# STM_BLOCK.net
KiCad netlist of a schematic drawn in EAGLE
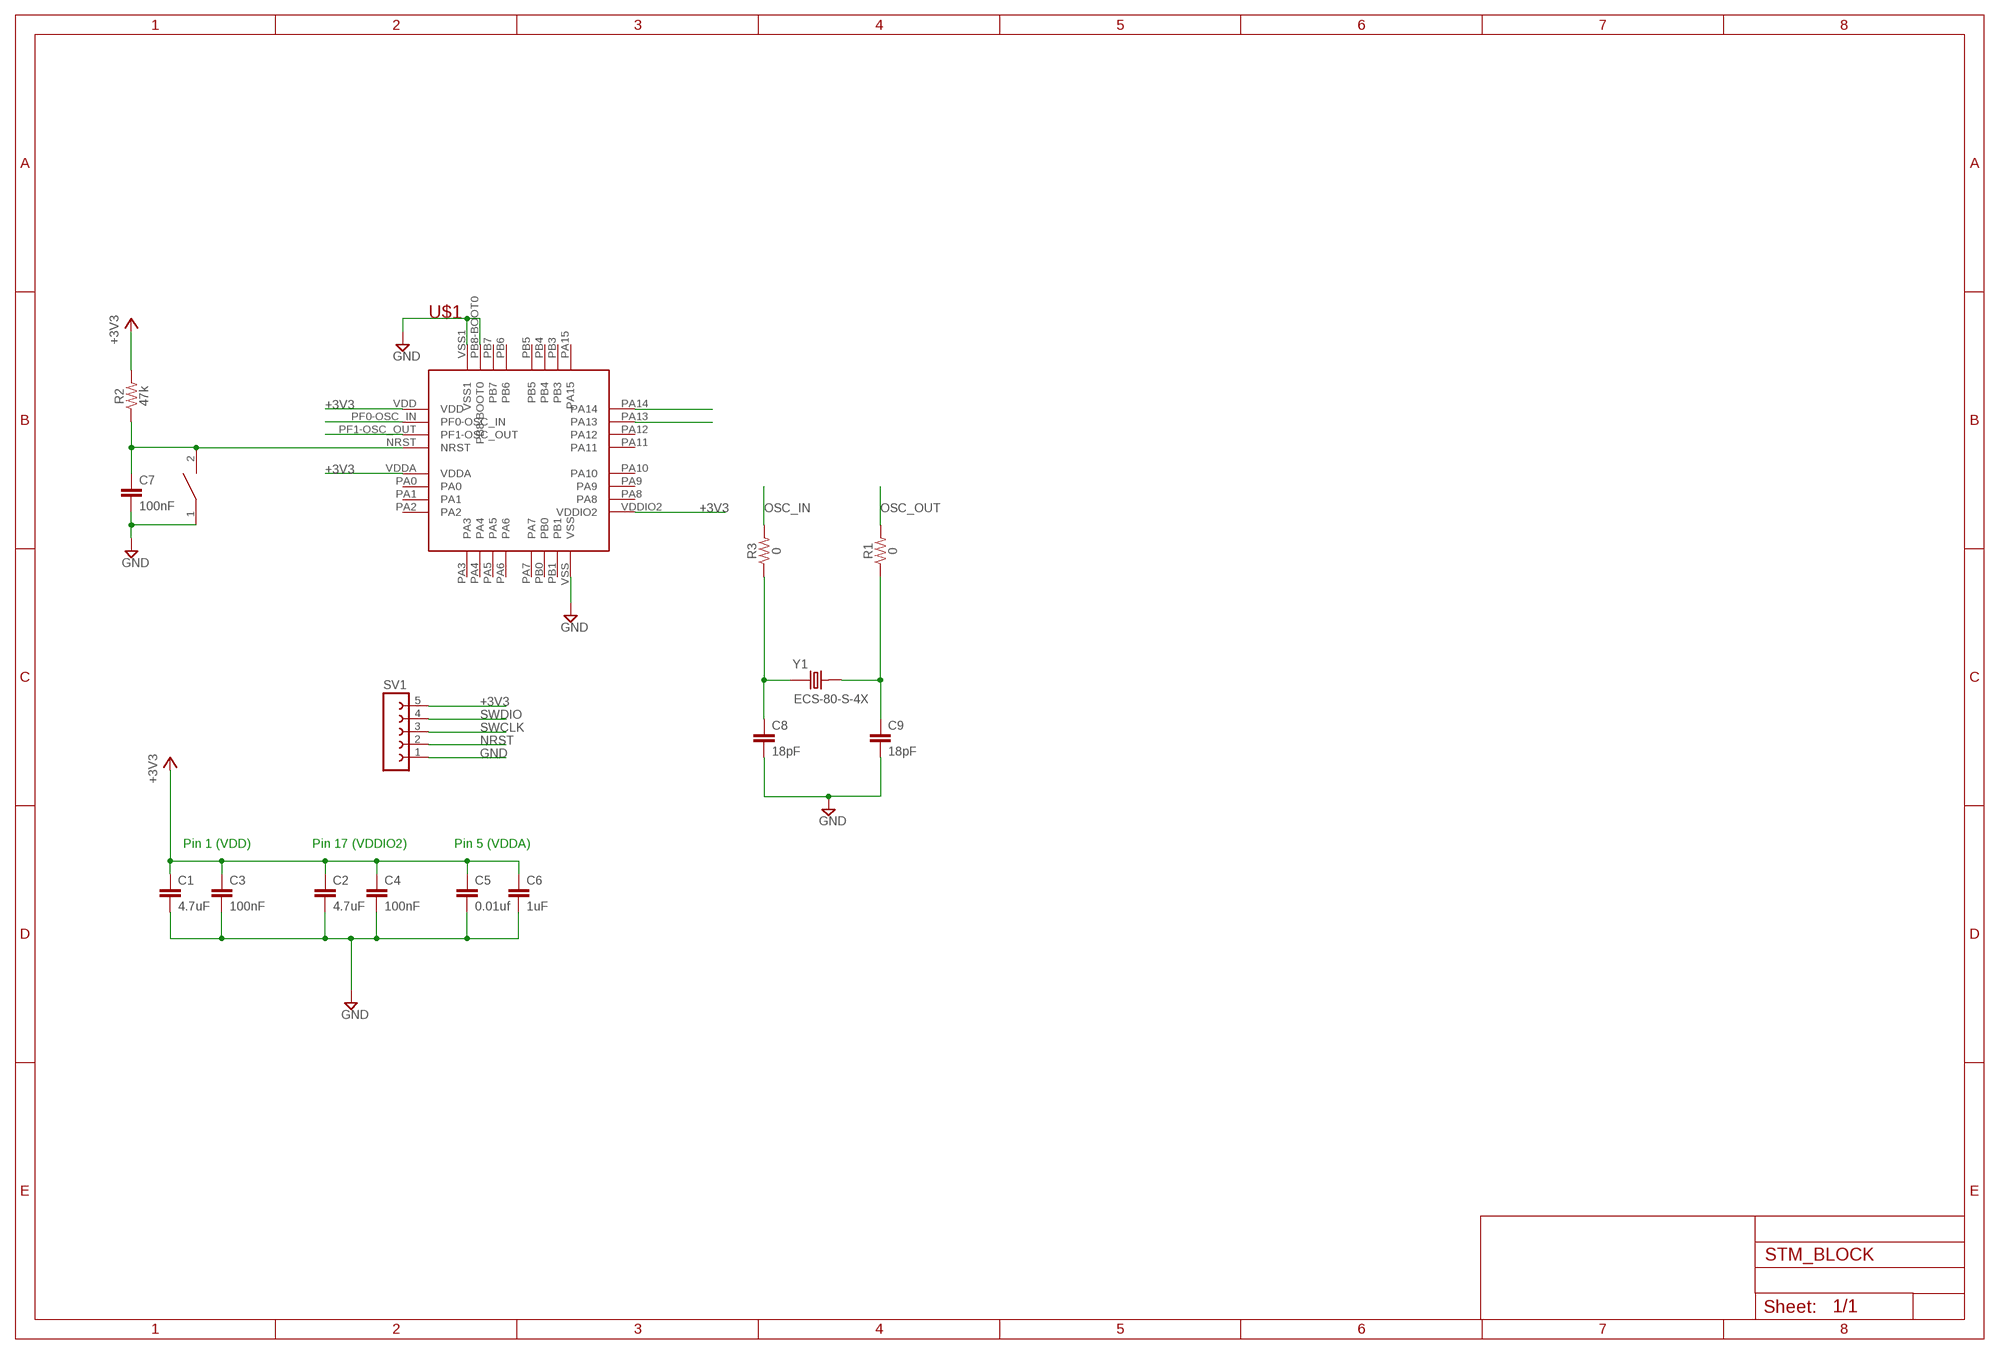
[diagram p0: schematic, sheet 1]

(export (version "E")
  (design (tool "Eeschema 10.0.6"))
  (components
    (comp (ref "C1")
      (value "4.7uF")
      (footprint "eagle-import:0603")
      (libsource (lib "eagle-import") (part "4.7UF0603"))
    )
    (comp (ref "C2")
      (value "4.7uF")
      (footprint "eagle-import:0603")
      (libsource (lib "eagle-import") (part "4.7UF0603"))
    )
    (comp (ref "C3")
      (value "100nF")
      (footprint "eagle-import:0603")
      (libsource (lib "eagle-import") (part "4.7UF0603"))
    )
    (comp (ref "C4")
      (value "100nF")
      (footprint "eagle-import:0603")
      (libsource (lib "eagle-import") (part "4.7UF0603"))
    )
    (comp (ref "C5")
      (value "0.01uf")
      (footprint "eagle-import:0603")
      (libsource (lib "eagle-import") (part "4.7UF0603"))
    )
    (comp (ref "C6")
      (value "1uF")
      (footprint "eagle-import:0603")
      (libsource (lib "eagle-import") (part "4.7UF0603"))
    )
    (comp (ref "C7")
      (value "100nF")
      (footprint "eagle-import:0603")
      (libsource (lib "eagle-import") (part "4.7UF0603"))
    )
    (comp (ref "C8")
      (value "18pF")
      (footprint "eagle-import:0603")
      (libsource (lib "eagle-import") (part "4.7UF0603"))
    )
    (comp (ref "C9")
      (value "18pF")
      (footprint "eagle-import:0603")
      (libsource (lib "eagle-import") (part "4.7UF0603"))
    )
    (comp (ref "R1")
      (value "0")
      (footprint "eagle-import:0603")
      (libsource (lib "eagle-import") (part "1KOHM-0603-1/10W-1%"))
    )
    (comp (ref "R2")
      (value "47k")
      (footprint "eagle-import:0603")
      (libsource (lib "eagle-import") (part "1KOHM-0603-1/10W-1%"))
    )
    (comp (ref "R3")
      (value "0")
      (footprint "eagle-import:0603")
      (libsource (lib "eagle-import") (part "1KOHM-0603-1/10W-1%"))
    )
    (comp (ref "RESET")
      (value "SWITCH")
      (footprint "eagle-import:SW_2512")
      (libsource (lib "eagle-import") (part "SWITCH"))
    )
    (comp (ref "SV1")
      (value "FE05-1")
      (footprint "eagle-import:FE05-1")
      (libsource (lib "eagle-import") (part "FE05-1"))
    )
    (comp (ref "U$1")
      (value "STM32F042K6T6")
      (footprint "eagle-import:STM32F042K6T6")
      (libsource (lib "eagle-import") (part "STM32F042K6T6"))
    )
    (comp (ref "Y1")
      (value "ECS-80-S-4X")
      (footprint "eagle-import:XTAL_ECS-80-S-4X")
      (fields (field (name "DIGI-KEY_PART_NUMBER") "X1057-ND") (field (name "MF") "ECS International"))
      (libsource (lib "eagle-import") (part "ECS-80-S-4X"))
    )
  )
  (nets
    (net (code "1") (name "+3V3") (class "Default")
      (node (ref "C1") (pin "1") (pinfunction "1_1") (pintype "passive"))
      (node (ref "C2") (pin "1") (pinfunction "1_1") (pintype "passive"))
      (node (ref "C3") (pin "1") (pinfunction "1_1") (pintype "passive"))
      (node (ref "C4") (pin "1") (pinfunction "1_1") (pintype "passive"))
      (node (ref "C5") (pin "1") (pinfunction "1_1") (pintype "passive"))
      (node (ref "C6") (pin "1") (pinfunction "1_1") (pintype "passive"))
      (node (ref "R2") (pin "2") (pinfunction "2_2") (pintype "passive"))
      (node (ref "SV1") (pin "5") (pinfunction "5_5") (pintype "passive"))
      (node (ref "U$1") (pin "VDD") (pinfunction "VDD_VDD") (pintype "bidirectional"))
      (node (ref "U$1") (pin "VDDA") (pinfunction "VDDA_VDDA") (pintype "bidirectional"))
      (node (ref "U$1") (pin "VDDIO2") (pinfunction "VDDIO2_VDDIO2") (pintype "bidirectional"))
    )
    (net (code "2") (name "/NRST") (class "Default")
      (node (ref "C7") (pin "1") (pinfunction "1_1") (pintype "passive"))
      (node (ref "R2") (pin "1") (pinfunction "1_1") (pintype "passive"))
      (node (ref "RESET") (pin "2") (pinfunction "P$2_2") (pintype "bidirectional"))
      (node (ref "SV1") (pin "2") (pinfunction "2_2") (pintype "passive"))
      (node (ref "U$1") (pin "NRST") (pinfunction "NRST_NRST") (pintype "bidirectional"))
    )
    (net (code "3") (name "/OSC_IN") (class "Default")
      (node (ref "R3") (pin "2") (pinfunction "2_2") (pintype "passive"))
      (node (ref "U$1") (pin "PF0-OSC_IN") (pinfunction "PF0-OSC_IN_PF0-OSC_IN") (pintype "bidirectional"))
    )
    (net (code "4") (name "/OSC_OUT") (class "Default")
      (node (ref "R1") (pin "2") (pinfunction "2_2") (pintype "passive"))
      (node (ref "U$1") (pin "PF1-OSC_OUT") (pinfunction "PF1-OSC_OUT_PF1-OSC_OUT") (pintype "bidirectional"))
    )
    (net (code "5") (name "/SWCLK") (class "Default")
      (node (ref "SV1") (pin "3") (pinfunction "3_3") (pintype "passive"))
      (node (ref "U$1") (pin "PA14") (pinfunction "PA14_PA14") (pintype "bidirectional"))
    )
    (net (code "6") (name "/SWDIO") (class "Default")
      (node (ref "SV1") (pin "4") (pinfunction "4_4") (pintype "passive"))
      (node (ref "U$1") (pin "PA13") (pinfunction "PA13_PA13") (pintype "bidirectional"))
    )
    (net (code "7") (name "GND") (class "Default")
      (node (ref "C1") (pin "2") (pinfunction "2_2") (pintype "passive"))
      (node (ref "C2") (pin "2") (pinfunction "2_2") (pintype "passive"))
      (node (ref "C3") (pin "2") (pinfunction "2_2") (pintype "passive"))
      (node (ref "C4") (pin "2") (pinfunction "2_2") (pintype "passive"))
      (node (ref "C5") (pin "2") (pinfunction "2_2") (pintype "passive"))
      (node (ref "C6") (pin "2") (pinfunction "2_2") (pintype "passive"))
      (node (ref "C7") (pin "2") (pinfunction "2_2") (pintype "passive"))
      (node (ref "C8") (pin "2") (pinfunction "2_2") (pintype "passive"))
      (node (ref "C9") (pin "2") (pinfunction "2_2") (pintype "passive"))
      (node (ref "RESET") (pin "1") (pinfunction "P$1_1") (pintype "bidirectional"))
      (node (ref "SV1") (pin "1") (pinfunction "1_1") (pintype "passive"))
      (node (ref "U$1") (pin "PB8-BOOT0") (pinfunction "PB8-BOOT0_PB8-BOOT0") (pintype "bidirectional"))
      (node (ref "U$1") (pin "VSS") (pinfunction "VSS_VSS") (pintype "bidirectional"))
      (node (ref "U$1") (pin "VSS1") (pinfunction "VSS1_VSS1") (pintype "bidirectional"))
    )
    (net (code "8") (name "Net-(C8-Pad1)") (class "Default")
      (node (ref "C8") (pin "1") (pinfunction "1_1") (pintype "passive"))
      (node (ref "R3") (pin "1") (pinfunction "1_1") (pintype "passive"))
      (node (ref "Y1") (pin "1") (pinfunction "1_1") (pintype "passive"))
    )
    (net (code "9") (name "Net-(C9-Pad1)") (class "Default")
      (node (ref "C9") (pin "1") (pinfunction "1_1") (pintype "passive"))
      (node (ref "R1") (pin "1") (pinfunction "1_1") (pintype "passive"))
      (node (ref "Y1") (pin "2") (pinfunction "2_2") (pintype "passive"))
    )
    (net (code "10") (name "unconnected-(U$1-PadPA0)") (class "Default")
      (node (ref "U$1") (pin "PA0") (pinfunction "PA0_PA0") (pintype "bidirectional"))
    )
    (net (code "11") (name "unconnected-(U$1-PadPA1)") (class "Default")
      (node (ref "U$1") (pin "PA1") (pinfunction "PA1_PA1") (pintype "bidirectional"))
    )
    (net (code "12") (name "unconnected-(U$1-PadPA2)") (class "Default")
      (node (ref "U$1") (pin "PA2") (pinfunction "PA2_PA2") (pintype "bidirectional"))
    )
    (net (code "13") (name "unconnected-(U$1-PadPA3)") (class "Default")
      (node (ref "U$1") (pin "PA3") (pinfunction "PA3_PA3") (pintype "bidirectional"))
    )
    (net (code "14") (name "unconnected-(U$1-PadPA4)") (class "Default")
      (node (ref "U$1") (pin "PA4") (pinfunction "PA4_PA4") (pintype "bidirectional"))
    )
    (net (code "15") (name "unconnected-(U$1-PadPA5)") (class "Default")
      (node (ref "U$1") (pin "PA5") (pinfunction "PA5_PA5") (pintype "bidirectional"))
    )
    (net (code "16") (name "unconnected-(U$1-PadPA6)") (class "Default")
      (node (ref "U$1") (pin "PA6") (pinfunction "PA6_PA6") (pintype "bidirectional"))
    )
    (net (code "17") (name "unconnected-(U$1-PadPA7)") (class "Default")
      (node (ref "U$1") (pin "PA7") (pinfunction "PA7_PA7") (pintype "bidirectional"))
    )
    (net (code "18") (name "unconnected-(U$1-PadPA8)") (class "Default")
      (node (ref "U$1") (pin "PA8") (pinfunction "PA8_PA8") (pintype "bidirectional"))
    )
    (net (code "19") (name "unconnected-(U$1-PadPA9)") (class "Default")
      (node (ref "U$1") (pin "PA9") (pinfunction "PA9_PA9") (pintype "bidirectional"))
    )
    (net (code "20") (name "unconnected-(U$1-PadPA10)") (class "Default")
      (node (ref "U$1") (pin "PA10") (pinfunction "PA10_PA10") (pintype "bidirectional"))
    )
    (net (code "21") (name "unconnected-(U$1-PadPA11)") (class "Default")
      (node (ref "U$1") (pin "PA11") (pinfunction "PA11_PA11") (pintype "bidirectional"))
    )
    (net (code "22") (name "unconnected-(U$1-PadPA12)") (class "Default")
      (node (ref "U$1") (pin "PA12") (pinfunction "PA12_PA12") (pintype "bidirectional"))
    )
    (net (code "23") (name "unconnected-(U$1-PadPA15)") (class "Default")
      (node (ref "U$1") (pin "PA15") (pinfunction "PA15_PA15") (pintype "bidirectional"))
    )
    (net (code "24") (name "unconnected-(U$1-PadPB0)") (class "Default")
      (node (ref "U$1") (pin "PB0") (pinfunction "PB0_PB0") (pintype "bidirectional"))
    )
    (net (code "25") (name "unconnected-(U$1-PadPB1)") (class "Default")
      (node (ref "U$1") (pin "PB1") (pinfunction "PB1_PB1") (pintype "bidirectional"))
    )
    (net (code "26") (name "unconnected-(U$1-PadPB3)") (class "Default")
      (node (ref "U$1") (pin "PB3") (pinfunction "PB3_PB3") (pintype "bidirectional"))
    )
    (net (code "27") (name "unconnected-(U$1-PadPB4)") (class "Default")
      (node (ref "U$1") (pin "PB4") (pinfunction "PB4_PB4") (pintype "bidirectional"))
    )
    (net (code "28") (name "unconnected-(U$1-PadPB5)") (class "Default")
      (node (ref "U$1") (pin "PB5") (pinfunction "PB5_PB5") (pintype "bidirectional"))
    )
    (net (code "29") (name "unconnected-(U$1-PadPB6)") (class "Default")
      (node (ref "U$1") (pin "PB6") (pinfunction "PB6_PB6") (pintype "bidirectional"))
    )
    (net (code "30") (name "unconnected-(U$1-PadPB7)") (class "Default")
      (node (ref "U$1") (pin "PB7") (pinfunction "PB7_PB7") (pintype "bidirectional"))
    )
  )
)
